# Snail-PCB-SCH_SH1__01.net
KiCad netlist of a schematic drawn in Altium Designer
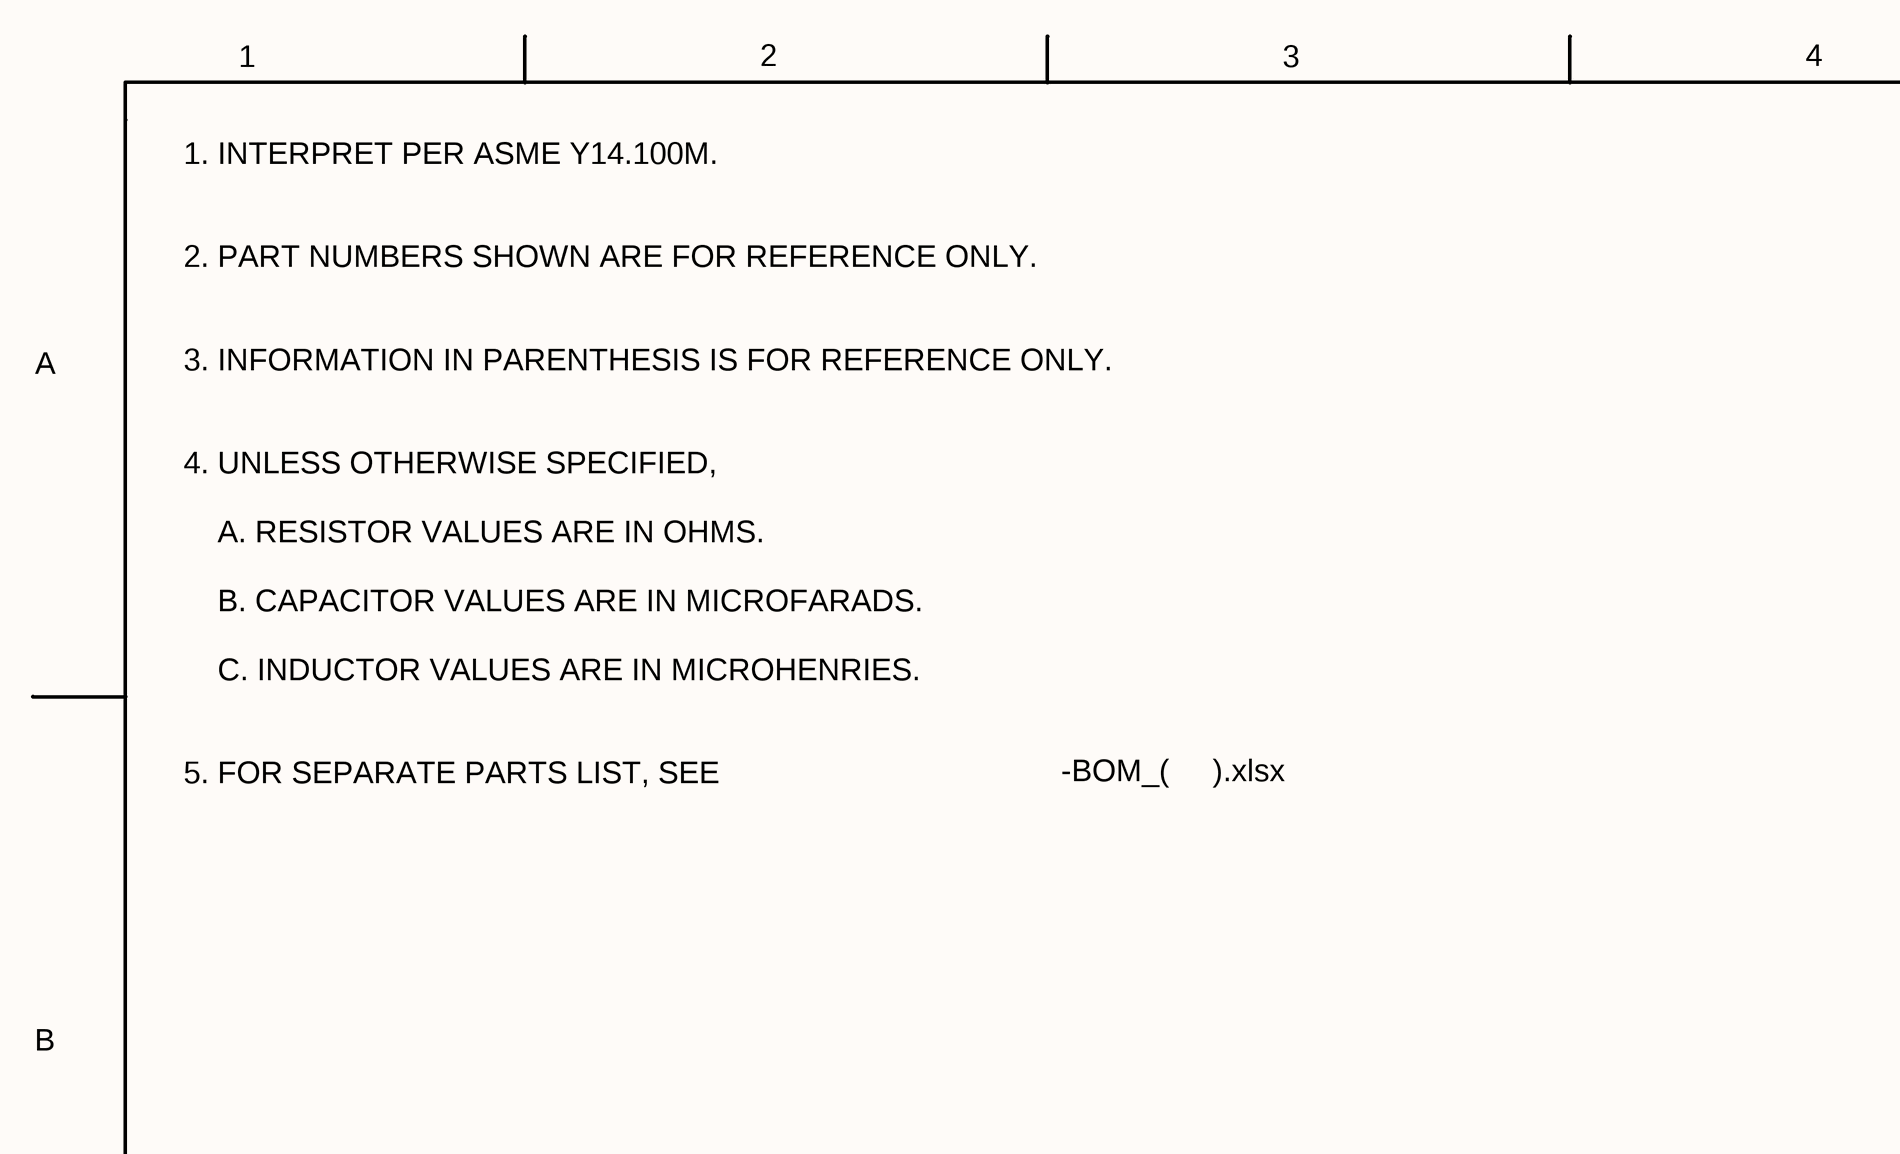
[diagram p0: Snail-PCB-SCH_SH1_(01).SchDoc, top left]
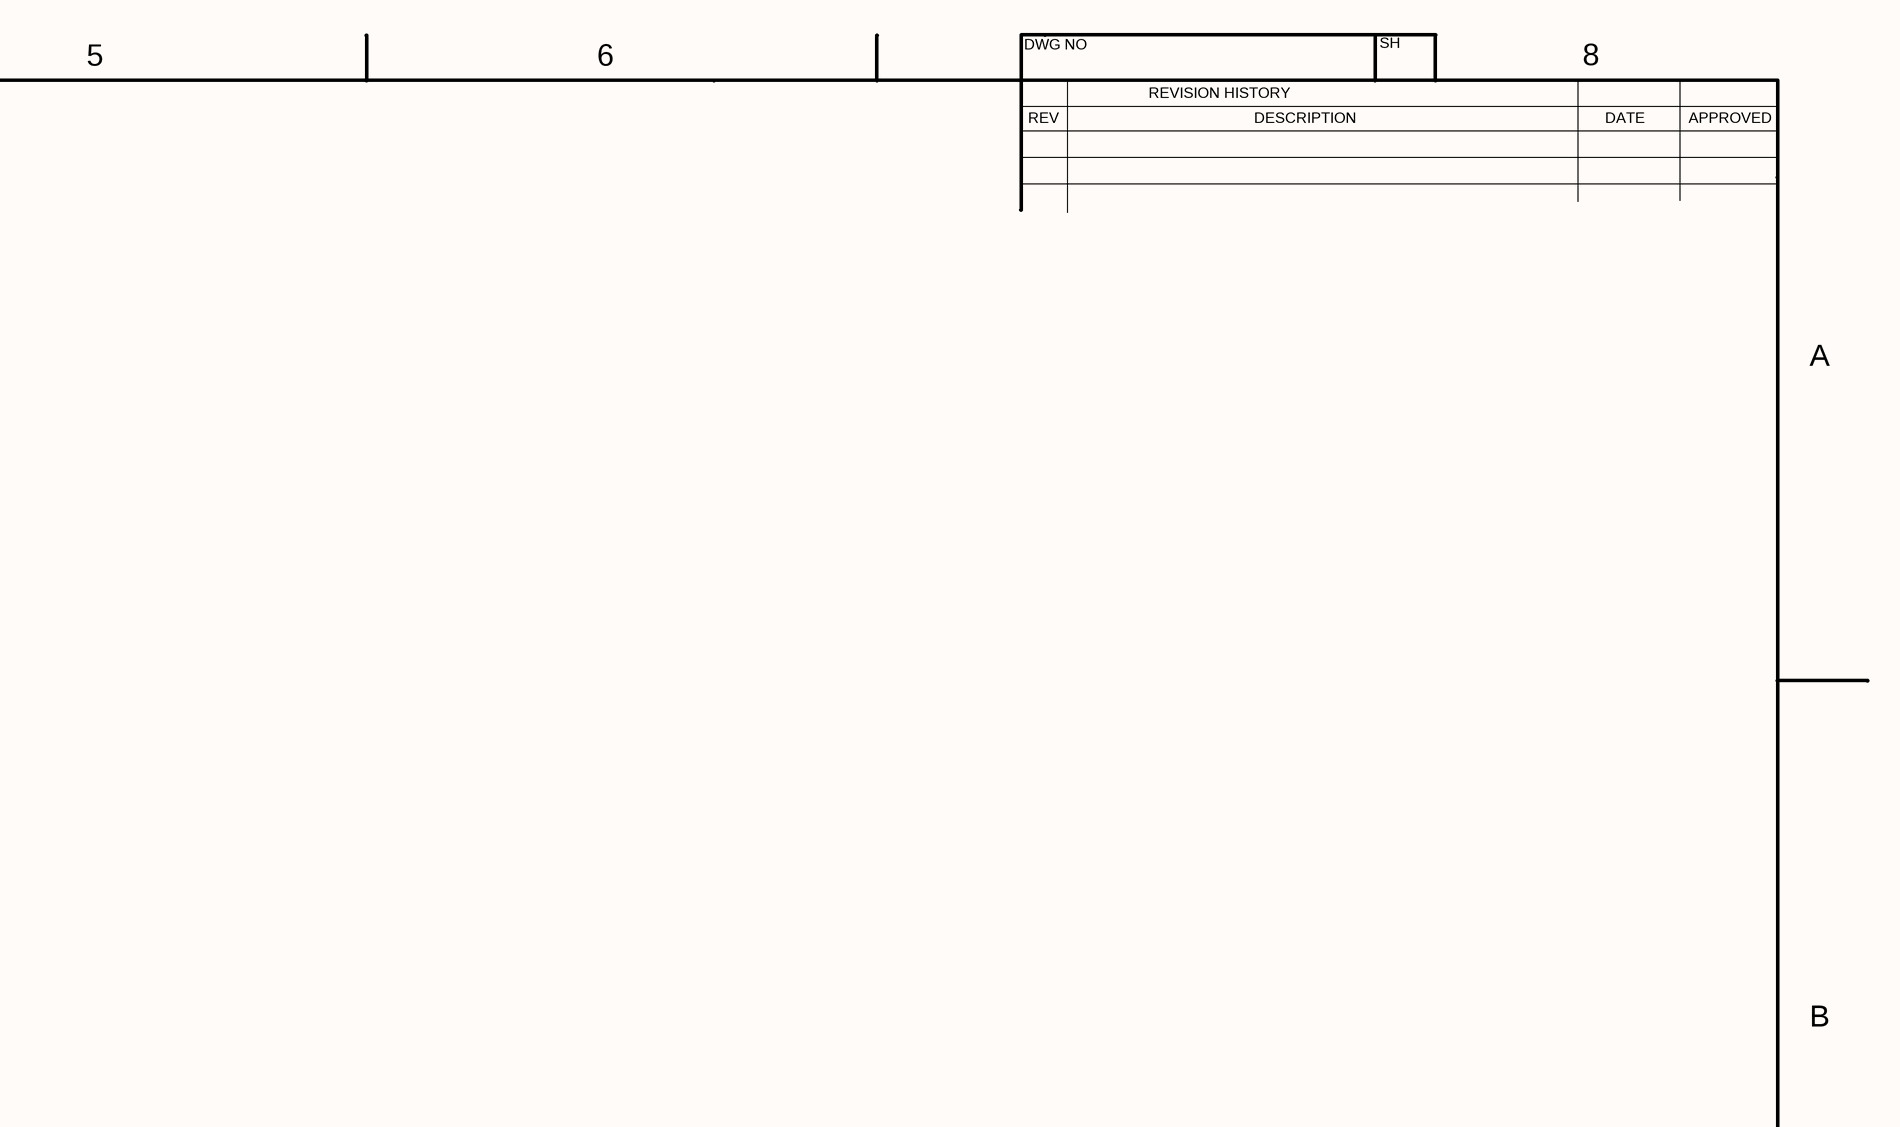
[diagram p1: Snail-PCB-SCH_SH1_(01).SchDoc, top right]
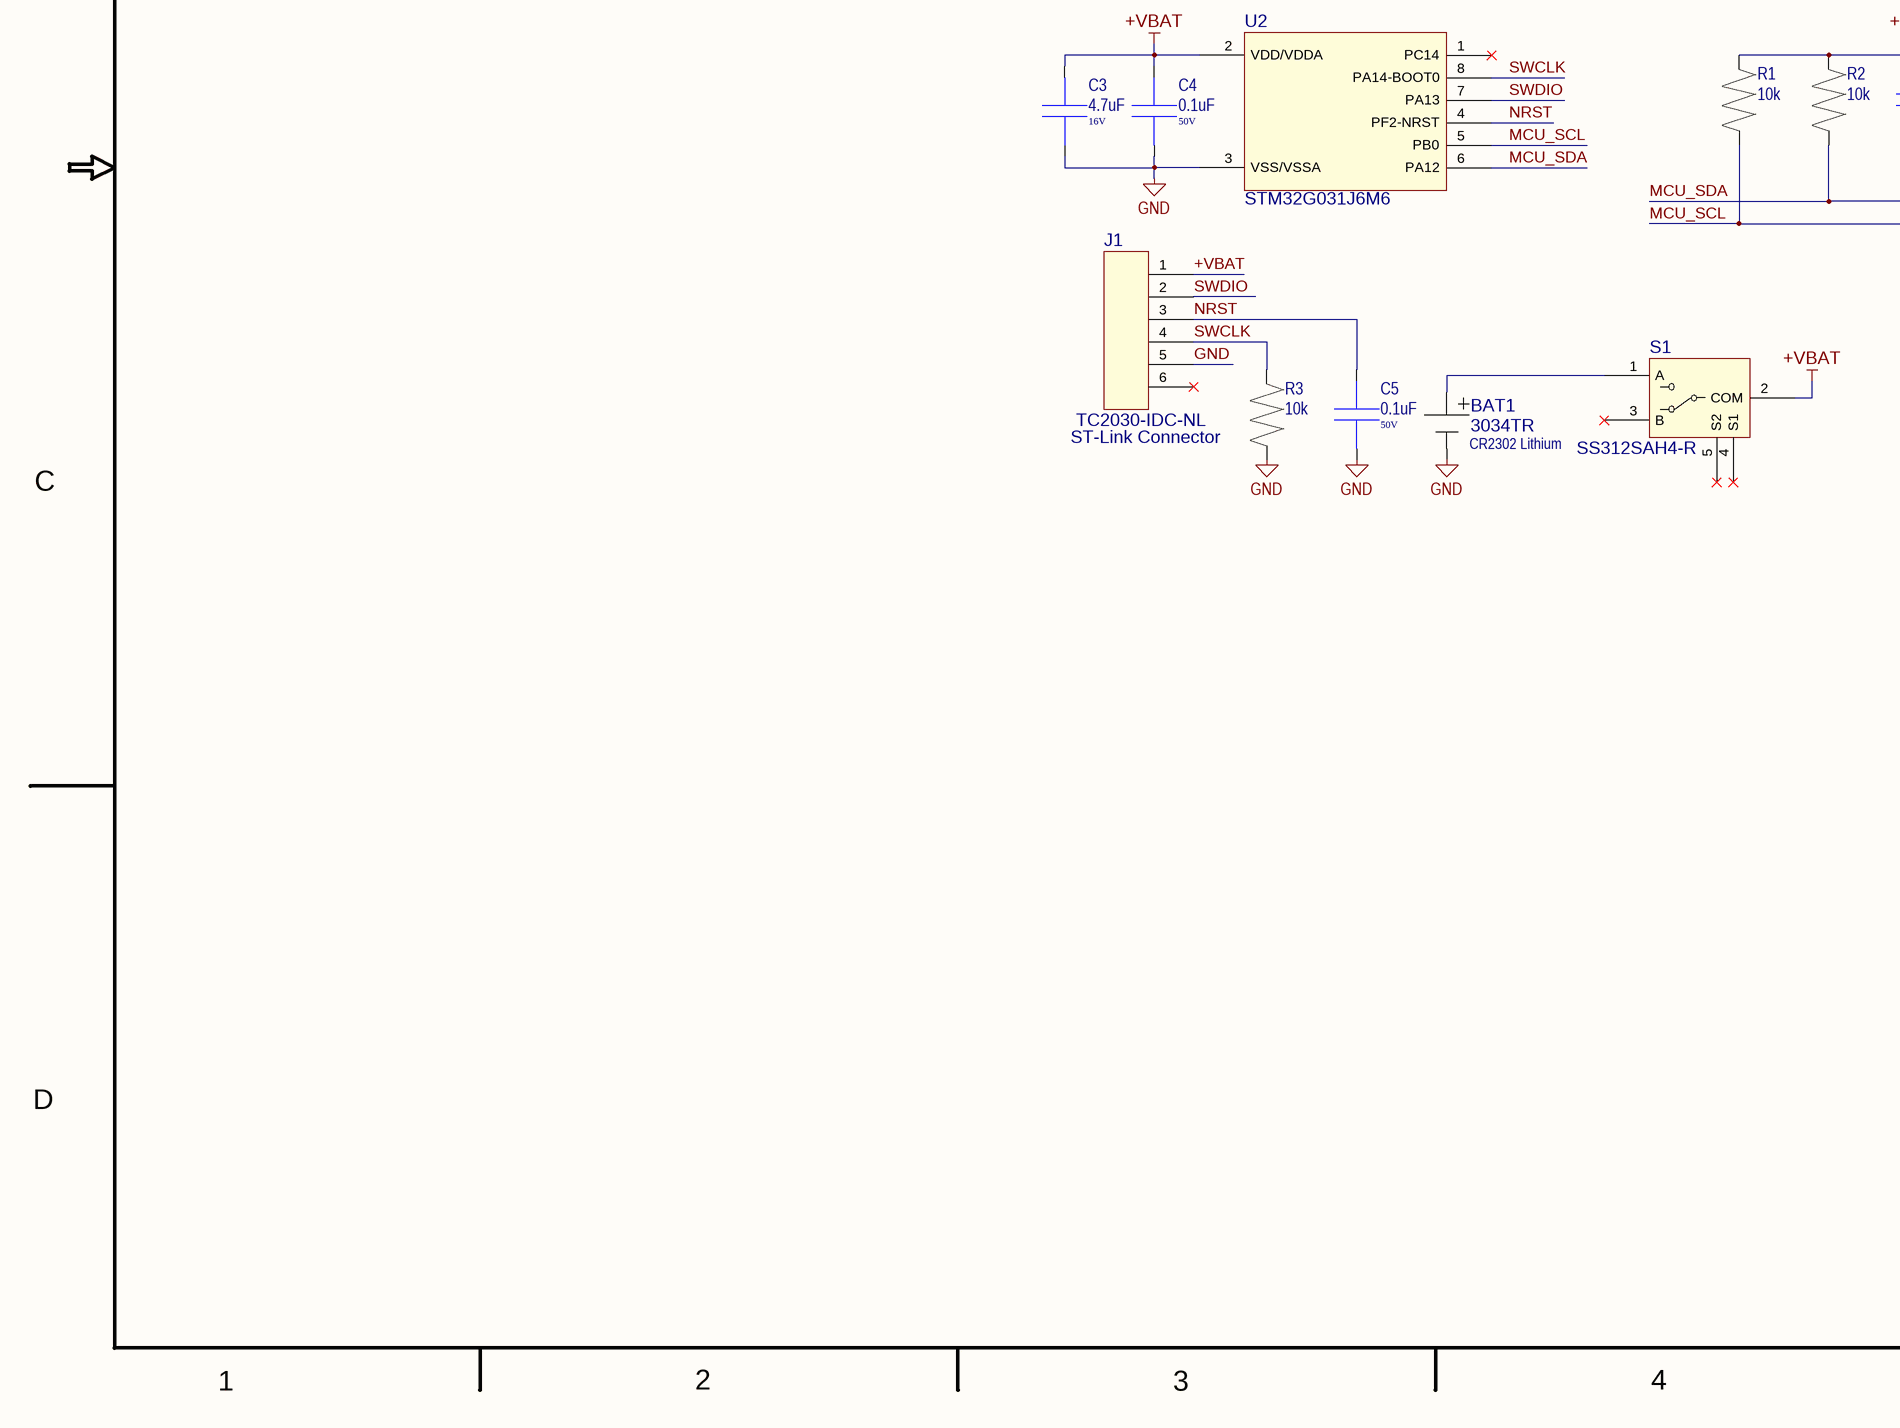
[diagram p2: Snail-PCB-SCH_SH1_(01).SchDoc, bottom left]
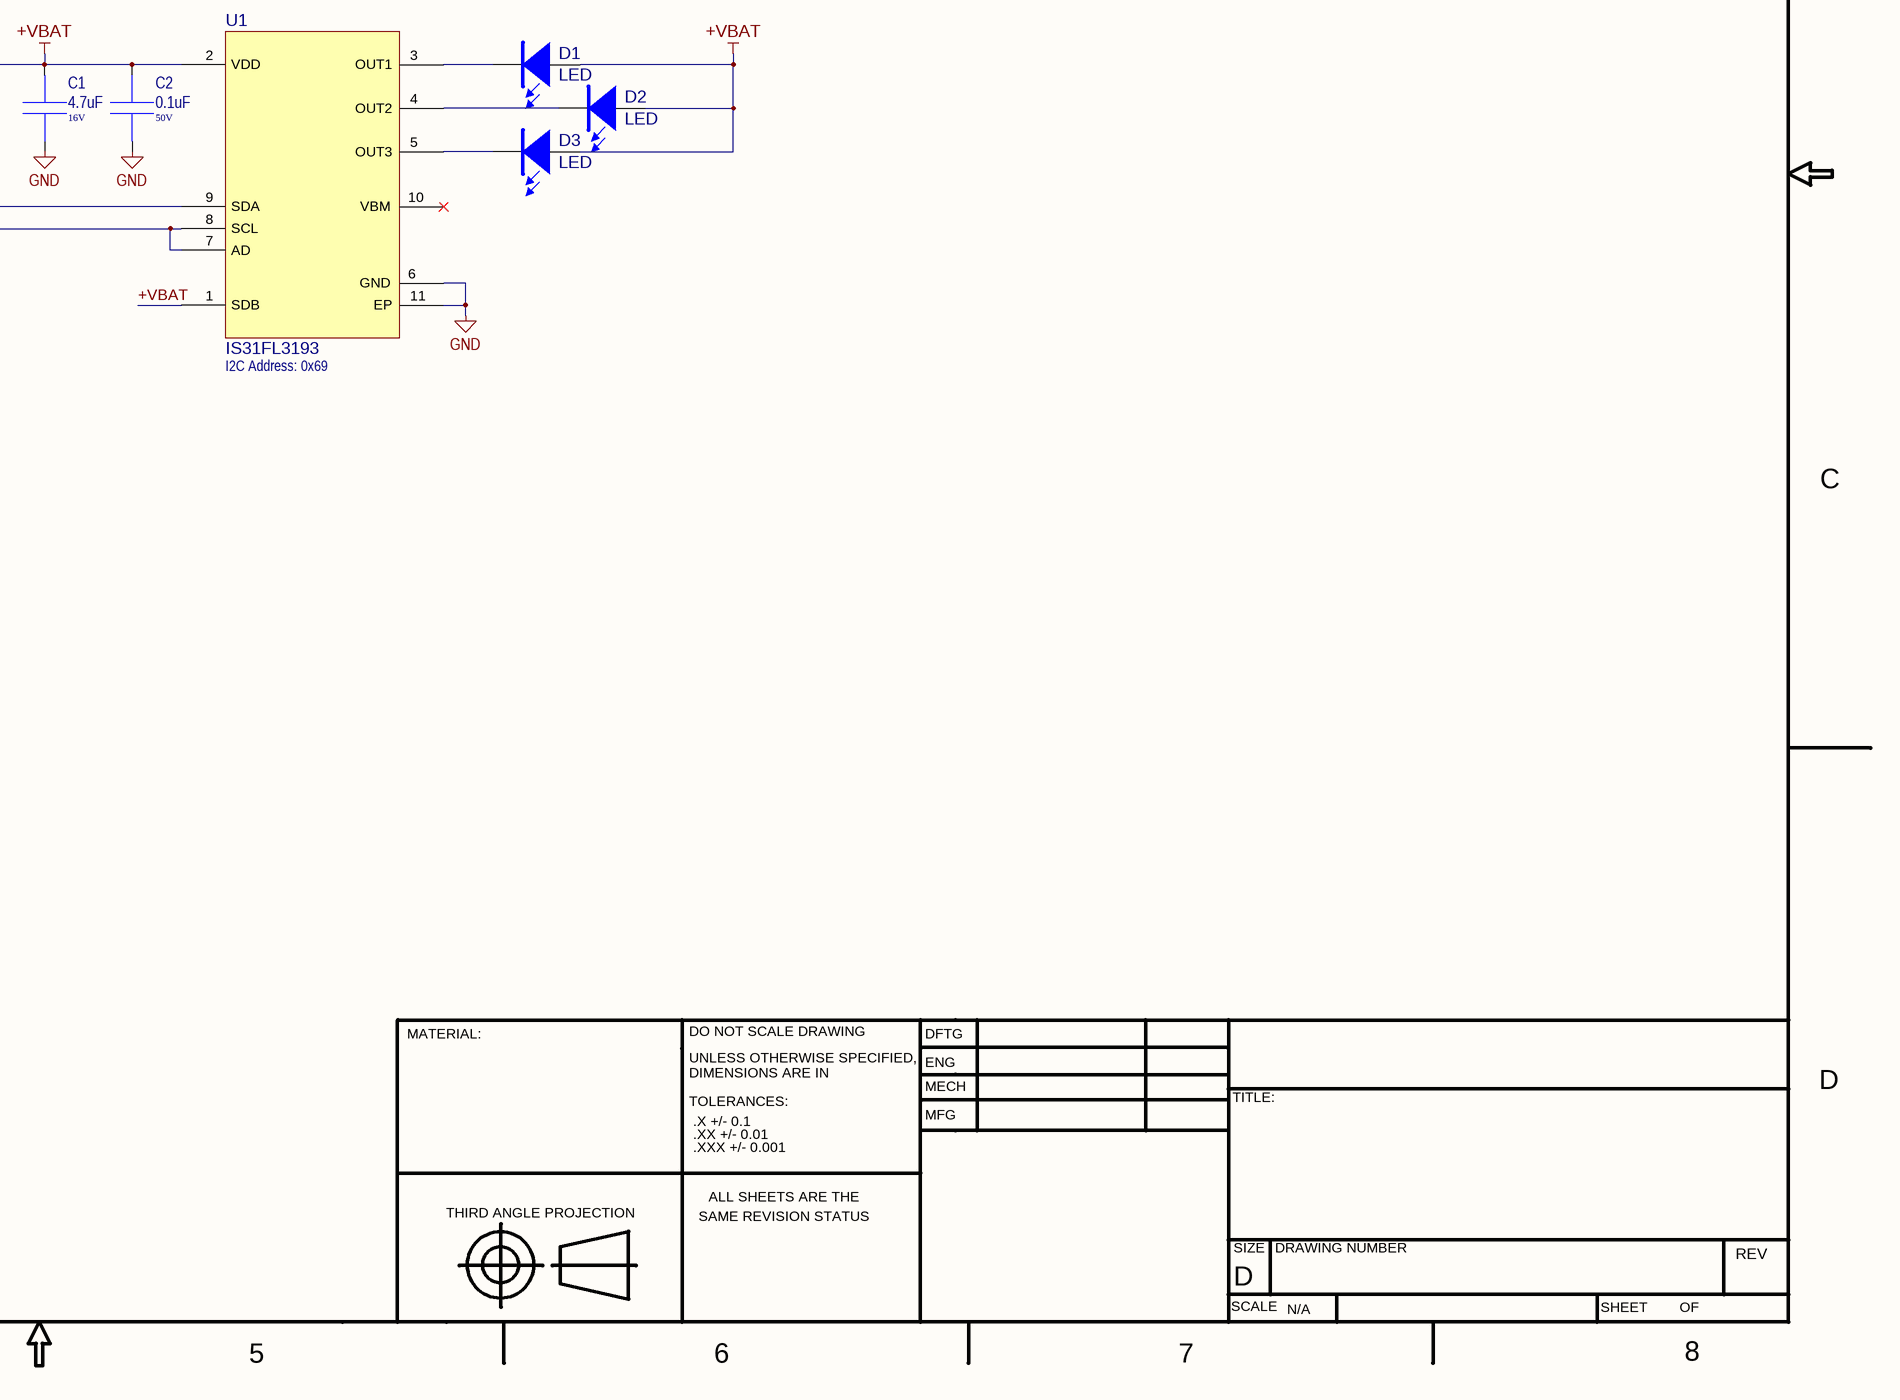
[diagram p3: Snail-PCB-SCH_SH1_(01).SchDoc, bottom right]

(export (version "E")
  (design (tool "Eeschema 10.0.6"))
  (components
    (comp (ref "BAT1")
      (value "3034TR")
      (footprint "BAT_3034")
      (description "BATT RETAINER COIN 20MM 1CEL SMD")
      (fields (field (name "MANUFACTURER") "Keystone Electronics"))
      (libsource (lib "ConnectorLib") (part "3034"))
    )
    (comp (ref "C1")
      (value "4.7uF")
      (footprint "0603")
      (description "CAP CER 4.7UF 16V X5R 0603")
      (fields
        (field (name "PART NUMBER") "CL10A475KO8NNNC")
        (field (name "MANUFACTURER") "Samsung Electro-Mechanics")
        (field (name "VOLTAGE") "16V")
      )
      (libsource (lib "CAPACITORS") (part "CAP"))
    )
    (comp (ref "C2")
      (value "0.1uF")
      (footprint "0603")
      (description "CAP CER 0.1UF 50V X7R 0603")
      (fields
        (field (name "PART NUMBER") "CL10B104KB8NFNC")
        (field (name "MANUFACTURER") "Samsung Electro-Mechanics")
        (field (name "VOLTAGE") "50V")
      )
      (libsource (lib "CAPACITORS") (part "CAP"))
    )
    (comp (ref "C3")
      (value "4.7uF")
      (footprint "0603")
      (description "CAP CER 4.7UF 16V X5R 0603")
      (fields
        (field (name "PART NUMBER") "CL10A475KO8NNNC")
        (field (name "MANUFACTURER") "Samsung Electro-Mechanics")
        (field (name "VOLTAGE") "16V")
      )
      (libsource (lib "CAPACITORS") (part "CAP"))
    )
    (comp (ref "C4")
      (value "0.1uF")
      (footprint "0603")
      (description "CAP CER 0.1UF 50V X7R 0603")
      (fields
        (field (name "PART NUMBER") "CL10B104KB8NFNC")
        (field (name "MANUFACTURER") "Samsung Electro-Mechanics")
        (field (name "VOLTAGE") "50V")
      )
      (libsource (lib "CAPACITORS") (part "CAP"))
    )
    (comp (ref "C5")
      (value "0.1uF")
      (footprint "0603")
      (description "CAP CER 0.1UF 50V X7R 0603")
      (fields
        (field (name "PART NUMBER") "CL10B104KB8NFNC")
        (field (name "MANUFACTURER") "Samsung Electro-Mechanics")
        (field (name "VOLTAGE") "50V")
      )
      (libsource (lib "CAPACITORS") (part "CAP"))
    )
    (comp (ref "D1")
      (value "LED")
      (footprint "0603_LED_Red")
      (description "LED HE RD 0603")
      (fields (field (name "PART NUMBER") "SM0603HCL") (field (name "MANUFACTURER") "Bivar"))
      (libsource (lib "SEMICONDUCTORS") (part "LED_Red"))
    )
    (comp (ref "D2")
      (value "LED")
      (footprint "0603_LED_Red")
      (description "LED HE RD 0603")
      (fields (field (name "PART NUMBER") "SM0603HCL") (field (name "MANUFACTURER") "Bivar"))
      (libsource (lib "SEMICONDUCTORS") (part "LED_Red"))
    )
    (comp (ref "D3")
      (value "LED")
      (footprint "0603_LED_Red")
      (description "LED HE RD 0603")
      (fields (field (name "PART NUMBER") "SM0603HCL") (field (name "MANUFACTURER") "Bivar"))
      (libsource (lib "SEMICONDUCTORS") (part "LED_Red"))
    )
    (comp (ref "J1")
      (value "TC2030-IDC-NL")
      (footprint "TC2030-IDC-NL-FP")
      (description "CBL PLUG-OF-NAILS 6-PIN")
      (fields (field (name "MANUFACTURER") "Tag-Connect LLC"))
      (libsource (lib "ConnectorLib") (part "TC2030-IDC-NL"))
    )
    (comp (ref "R1")
      (value "10k")
      (footprint "0603")
      (description "RES SMD 10K OHM 1% 1/5W 0603")
      (fields (field (name "PART NUMBER") "CR0603-FX-1002ELF") (field (name "MANUFACTURER") "Bourns"))
      (libsource (lib "RESISTORS") (part "RES"))
    )
    (comp (ref "R2")
      (value "10k")
      (footprint "0603")
      (description "RES SMD 10K OHM 1% 1/5W 0603")
      (fields (field (name "PART NUMBER") "CR0603-FX-1002ELF") (field (name "MANUFACTURER") "Bourns"))
      (libsource (lib "RESISTORS") (part "RES"))
    )
    (comp (ref "R3")
      (value "10k")
      (footprint "0603")
      (description "RES SMD 10K OHM 1% 1/5W 0603")
      (fields (field (name "PART NUMBER") "CR0603-FX-1002ELF") (field (name "MANUFACTURER") "Bourns"))
      (libsource (lib "RESISTORS") (part "RES"))
    )
    (comp (ref "S1")
      (value "SS312SAH4-R")
      (footprint "SW_SS312SAH4-R")
      (description "SWITCH SLIDE SPDT 0.4VA 28V")
      (fields (field (name "MANUFACTURER") "NKK Switches"))
      (libsource (lib "SwitchesLib") (part "SS312SAH4-R"))
    )
    (comp (ref "U1")
      (value "IS31FL3193")
      (footprint "DFN-10")
      (description "IC LED DRIVER LINEAR 42MA 10DFN")
      (fields
        (field (name "MANUFACTURER") "Lumissil Microsystems")
        (field (name "PART NUMBER") "IS31FL3193-DLS2-TR")
      )
      (libsource (lib "LED Drivers") (part "IS31FL3193"))
    )
    (comp (ref "U2")
      (value "STM32G031J6M6")
      (footprint "SOIC-8")
      (description "IC MCU 32BIT 32KB FLASH 8SO")
      (fields (field (name "MANUFACTURER") "STMicroelectronics"))
      (libsource (lib "MicrocontrollerUnits") (part "STM32G031J6M6"))
    )
  )
  (nets
    (net (code "1") (name "+VBAT") (class "Default")
      (node (ref "C1") (pin "1") (pinfunction "1_1") (pintype "passive"))
      (node (ref "C2") (pin "2") (pinfunction "2_2") (pintype "passive"))
      (node (ref "C3") (pin "1") (pinfunction "1_1") (pintype "passive"))
      (node (ref "C4") (pin "2") (pinfunction "2_2") (pintype "passive"))
      (node (ref "D1") (pin "1") (pinfunction "A_1") (pintype "passive"))
      (node (ref "D2") (pin "1") (pinfunction "A_1") (pintype "passive"))
      (node (ref "D3") (pin "1") (pinfunction "A_1") (pintype "passive"))
      (node (ref "J1") (pin "1") (pinfunction "1_1") (pintype "passive"))
      (node (ref "R1") (pin "1") (pinfunction "1_1") (pintype "passive"))
      (node (ref "R2") (pin "1") (pinfunction "1_1") (pintype "passive"))
      (node (ref "S1") (pin "2") (pinfunction "COM_2") (pintype "passive"))
      (node (ref "U1") (pin "1") (pinfunction "SDB_1") (pintype "passive"))
      (node (ref "U1") (pin "2") (pinfunction "VDD_2") (pintype "passive"))
      (node (ref "U2") (pin "2") (pinfunction "VDD/VDDA_2") (pintype "passive"))
    )
    (net (code "2") (name "/MCU_SCL") (class "Default")
      (node (ref "R1") (pin "2") (pinfunction "2_2") (pintype "passive"))
      (node (ref "U1") (pin "7") (pinfunction "AD_7") (pintype "passive"))
      (node (ref "U1") (pin "8") (pinfunction "SCL_8") (pintype "passive"))
      (node (ref "U2") (pin "5") (pinfunction "PB0_5") (pintype "power_in"))
    )
    (net (code "3") (name "/MCU_SDA") (class "Default")
      (node (ref "R2") (pin "2") (pinfunction "2_2") (pintype "passive"))
      (node (ref "U1") (pin "9") (pinfunction "SDA_9") (pintype "passive"))
      (node (ref "U2") (pin "6") (pinfunction "PA12_6") (pintype "passive"))
    )
    (net (code "4") (name "/NRST") (class "Default")
      (node (ref "C5") (pin "2") (pinfunction "2_2") (pintype "passive"))
      (node (ref "J1") (pin "3") (pinfunction "3_3") (pintype "passive"))
      (node (ref "U2") (pin "4") (pinfunction "PF2-NRST_4") (pintype "power_in"))
    )
    (net (code "5") (name "/SWCLK") (class "Default")
      (node (ref "J1") (pin "4") (pinfunction "4_4") (pintype "passive"))
      (node (ref "R3") (pin "1") (pinfunction "1_1") (pintype "passive"))
      (node (ref "U2") (pin "8") (pinfunction "PA14-BOOT0_8") (pintype "passive"))
    )
    (net (code "6") (name "/SWDIO") (class "Default")
      (node (ref "J1") (pin "2") (pinfunction "2_2") (pintype "passive"))
      (node (ref "U2") (pin "7") (pinfunction "PA13_7") (pintype "passive"))
    )
    (net (code "7") (name "GND") (class "Default")
      (node (ref "BAT1") (pin "2") (pinfunction "2_2") (pintype "passive"))
      (node (ref "C1") (pin "2") (pinfunction "2_2") (pintype "passive"))
      (node (ref "C2") (pin "1") (pinfunction "1_1") (pintype "passive"))
      (node (ref "C3") (pin "2") (pinfunction "2_2") (pintype "passive"))
      (node (ref "C4") (pin "1") (pinfunction "1_1") (pintype "passive"))
      (node (ref "C5") (pin "1") (pinfunction "1_1") (pintype "passive"))
      (node (ref "J1") (pin "5") (pinfunction "5_5") (pintype "passive"))
      (node (ref "R3") (pin "2") (pinfunction "2_2") (pintype "passive"))
      (node (ref "U1") (pin "11") (pinfunction "EP_11") (pintype "passive"))
      (node (ref "U1") (pin "6") (pinfunction "GND_6") (pintype "passive"))
      (node (ref "U2") (pin "3") (pinfunction "VSS/VSSA_3") (pintype "passive"))
    )
    (net (code "8") (name "Net-(D1-K)") (class "Default")
      (node (ref "D1") (pin "2") (pinfunction "K_2") (pintype "passive"))
      (node (ref "U1") (pin "3") (pinfunction "OUT1_3") (pintype "passive"))
    )
    (net (code "9") (name "Net-(D2-K)") (class "Default")
      (node (ref "D2") (pin "2") (pinfunction "K_2") (pintype "passive"))
      (node (ref "U1") (pin "4") (pinfunction "OUT2_4") (pintype "passive"))
    )
    (net (code "10") (name "Net-(D3-K)") (class "Default")
      (node (ref "D3") (pin "2") (pinfunction "K_2") (pintype "passive"))
      (node (ref "U1") (pin "5") (pinfunction "OUT3_5") (pintype "passive"))
    )
    (net (code "11") (name "Net-(S1-A)") (class "Default")
      (node (ref "BAT1") (pin "1") (pinfunction "1_1") (pintype "passive"))
      (node (ref "S1") (pin "1") (pinfunction "A_1") (pintype "passive"))
    )
    (net (code "12") (name "unconnected-(J1-Pad6)") (class "Default")
      (node (ref "J1") (pin "6") (pinfunction "6_6") (pintype "passive+no_connect"))
    )
    (net (code "13") (name "unconnected-(S1-B-Pad3)") (class "Default")
      (node (ref "S1") (pin "3") (pinfunction "B_3") (pintype "passive+no_connect"))
    )
    (net (code "14") (name "unconnected-(S1-S1-Pad4)") (class "Default")
      (node (ref "S1") (pin "4") (pinfunction "S1_4") (pintype "passive+no_connect"))
    )
    (net (code "15") (name "unconnected-(S1-S2-Pad5)") (class "Default")
      (node (ref "S1") (pin "5") (pinfunction "S2_5") (pintype "passive+no_connect"))
    )
    (net (code "16") (name "unconnected-(U1-VBM-Pad10)") (class "Default")
      (node (ref "U1") (pin "10") (pinfunction "VBM_10") (pintype "passive+no_connect"))
    )
    (net (code "17") (name "unconnected-(U2-PC14-Pad1)") (class "Default")
      (node (ref "U2") (pin "1") (pinfunction "PC14_1") (pintype "passive+no_connect"))
    )
  )
)
